# Sheet1.net
KiCad netlist of a schematic drawn in Altium Designer
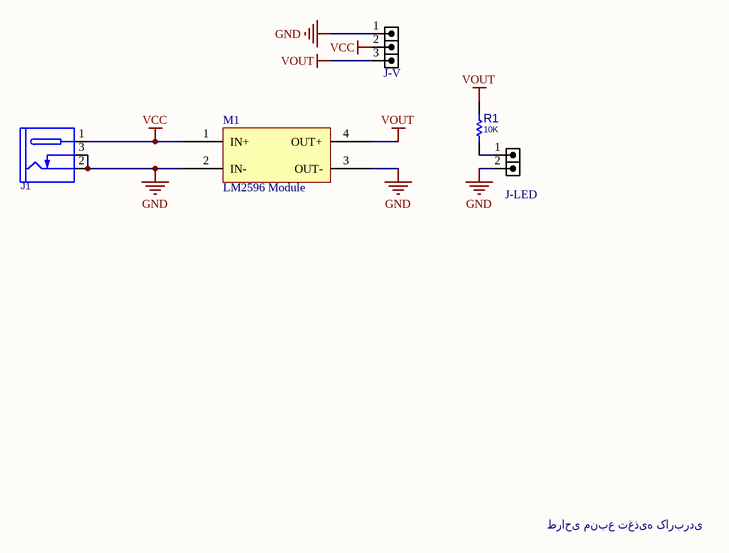
[diagram p0: Sheet1.SchDoc]

(export (version "E")
  (design (tool "Eeschema 10.0.6"))
  (components
    (comp (ref "J-LED")
      (value "HDRM2")
      (footprint "HDR_M_1X2")
      (description "CONN, HEADER, Male, pitch: 2.54mm, 2POS")
      (libsource (lib "conn_header_2.54mm_st") (part "HDR_M_1X2"))
    )
    (comp (ref "J-V")
      (value "HDRM3")
      (footprint "HDR_M_1X3")
      (description "CONN, HEADER, Male, pitch: 2.54mm, 3POS")
      (libsource (lib "conn_header_2.54mm_st") (part "HDR_M_1X3"))
    )
    (comp (ref "J1")
      (value "DC_POWER_JACK")
      (footprint "JAC_PWR2")
      (description "CONN, PWR JACK DC, PLUG DIAM 2.0MM RA THD")
      (fields
        (field (name "MANF") "CUI STACK")
        (field (name "MANF_P#") "PJ-202A, PJ-002AH, PJ-102AH, KLDX-0202")
      )
      (libsource (lib "conn_powerJack") (part "CONN_PWR_JACKR2"))
    )
    (comp (ref "M1")
      (value "LM2596 Module")
      (footprint "DC-DC-MODULE")
      (description "LM2596 , Power Module ,  Step-Down Voltage Regulator Module")
      (libsource (lib "Schlib1") (part "MODULE-DC-DC"))
    )
    (comp (ref "R1")
      (value "10K")
      (footprint "R025W_AX04")
      (description "RESISTOR, THD")
      (fields (field (name "MANF_P#") "RK73H1ETTP4701F") (field (name "MANF") "KOA SPEER"))
      (libsource (lib "passive") (part "RES_THD"))
    )
  )
  (nets
    (net (code "1") (name "GND") (class "Default")
      (node (ref "J-LED") (pin "2") (pinfunction "2_2") (pintype "passive"))
      (node (ref "J-V") (pin "1") (pinfunction "1_1") (pintype "passive"))
      (node (ref "J1") (pin "2") (pinfunction "SLEEVE_2") (pintype "power_in"))
      (node (ref "J1") (pin "3") (pinfunction "INSERTION_DET_3") (pintype "power_in"))
      (node (ref "M1") (pin "2") (pinfunction "IN-_2") (pintype "passive"))
      (node (ref "M1") (pin "3") (pinfunction "OUT-_3") (pintype "passive"))
    )
    (net (code "2") (name "Net-(J-LED-Pad1)") (class "Default")
      (node (ref "J-LED") (pin "1") (pinfunction "1_1") (pintype "passive"))
      (node (ref "R1") (pin "1") (pinfunction "1_1") (pintype "passive"))
    )
    (net (code "3") (name "VCC") (class "Default")
      (node (ref "J-V") (pin "2") (pinfunction "2_2") (pintype "passive"))
      (node (ref "J1") (pin "1") (pinfunction "TIP_1") (pintype "power_in"))
      (node (ref "M1") (pin "1") (pinfunction "IN+_1") (pintype "passive"))
    )
    (net (code "4") (name "VOUT") (class "Default")
      (node (ref "J-V") (pin "3") (pinfunction "3_3") (pintype "passive"))
      (node (ref "M1") (pin "4") (pinfunction "OUT+_4") (pintype "passive"))
      (node (ref "R1") (pin "2") (pinfunction "2_2") (pintype "passive"))
    )
  )
)
